# Sheet_1_2020-07-27_09-10-22.net
KiCad netlist of a schematic drawn in Altium Designer
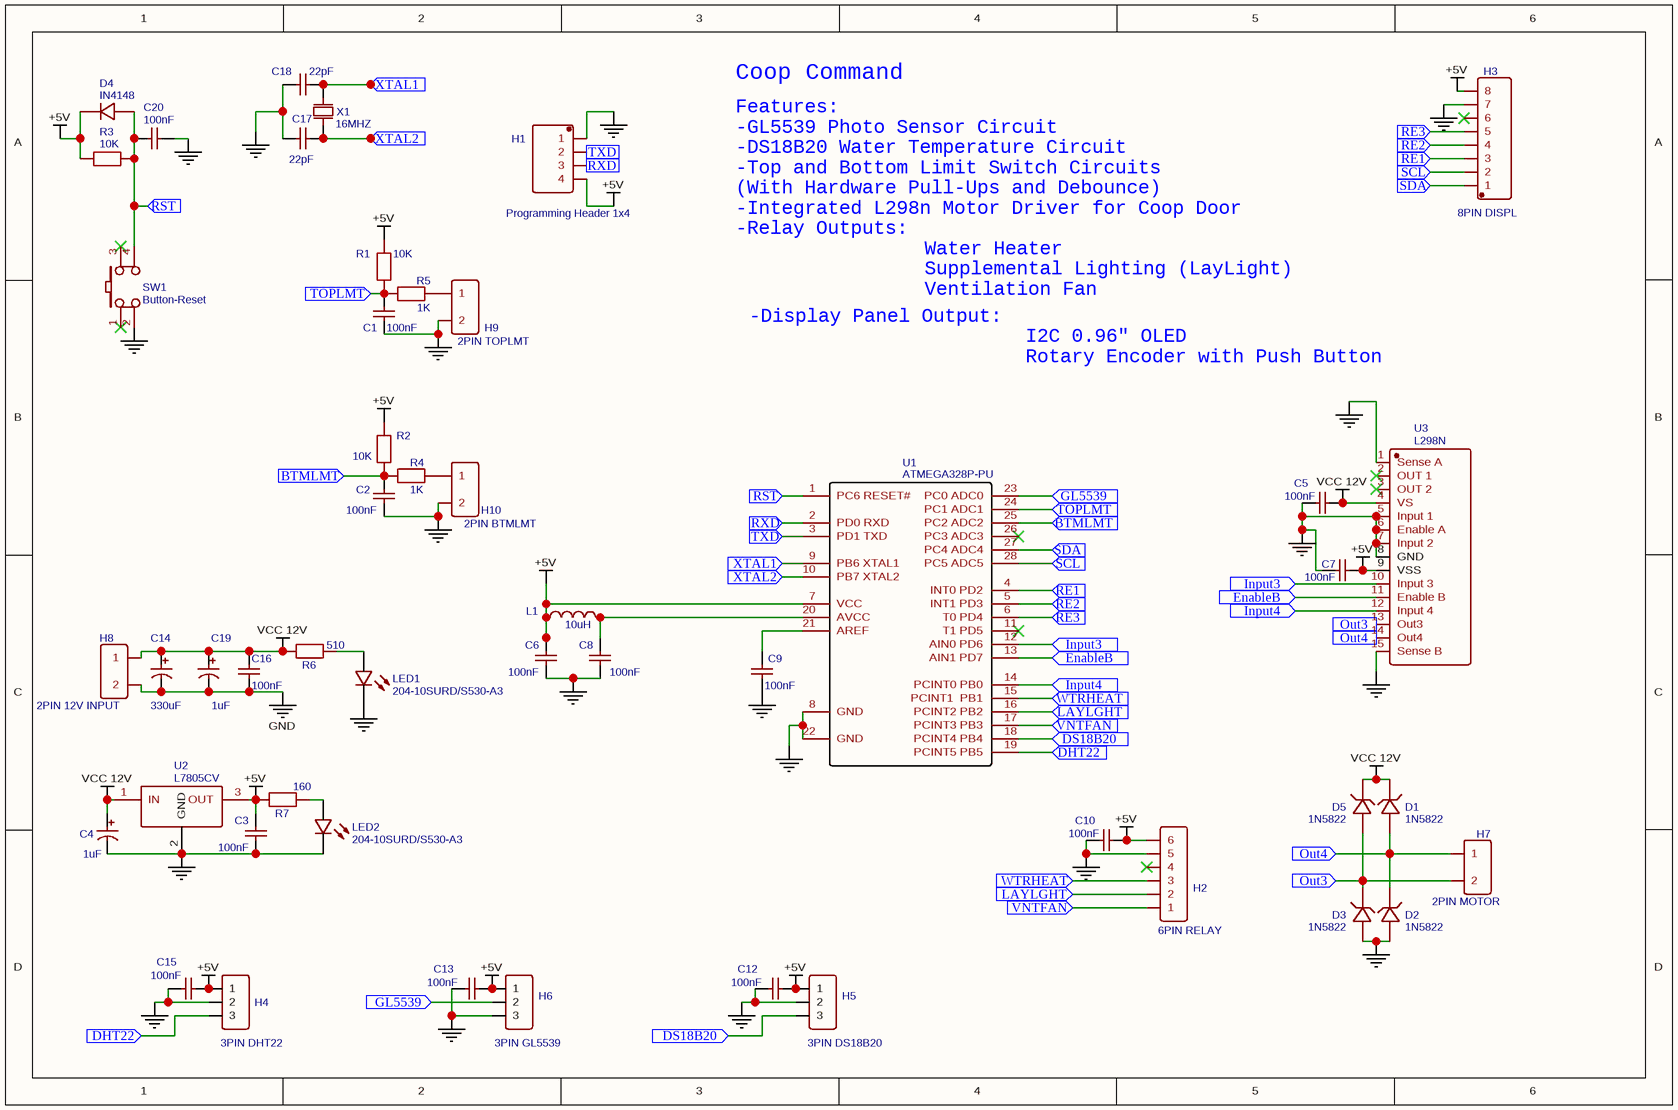
[diagram p0: Sheet_1_2020-07-27_09-10-22.schdoc]

(export (version "E")
  (design (tool "Eeschema 10.0.6"))
  (components
    (comp (ref "C1")
      (value "100nF")
      (fields
        (field (name "BOM_MANUFACTURER PART") "CS1F5.6Y5V1A104Z")
        (field (name "BOM_SUPPLIER PART") "C9306")
      )
      (libsource (lib "altium-import") (part "root_3_100nF_"))
    )
    (comp (ref "C2")
      (value "100nF")
      (fields
        (field (name "BOM_MANUFACTURER PART") "CS1F5.6Y5V1A104Z")
        (field (name "BOM_SUPPLIER PART") "C9306")
      )
      (libsource (lib "altium-import") (part "root_3_100nF_"))
    )
    (comp (ref "C3")
      (value "100nF")
      (fields
        (field (name "BOM_MANUFACTURER PART") "CS1F5.6Y5V1A104Z")
        (field (name "BOM_SUPPLIER PART") "C9306")
      )
      (libsource (lib "altium-import") (part "root_3_100nF_"))
    )
    (comp (ref "C4")
      (value "1uF")
      (fields
        (field (name "BOM_MANUFACTURER PART") "1uF 50V 4*5")
        (field (name "BOM_SUPPLIER PART") "C47848")
      )
      (libsource (lib "altium-import") (part "root_3_1uF_"))
    )
    (comp (ref "C5")
      (value "100nF")
      (fields
        (field (name "BOM_MANUFACTURER PART") "CS1F5.6Y5V1A104Z")
        (field (name "BOM_SUPPLIER PART") "C9306")
      )
      (libsource (lib "altium-import") (part "root_0_100nF_"))
    )
    (comp (ref "C6")
      (value "100nF")
      (fields
        (field (name "BOM_MANUFACTURER PART") "CS1F5.6Y5V1A104Z")
        (field (name "BOM_SUPPLIER PART") "C9306")
      )
      (libsource (lib "altium-import") (part "root_3_100nF_"))
    )
    (comp (ref "C7")
      (value "100nF")
      (fields
        (field (name "BOM_MANUFACTURER PART") "CS1F5.6Y5V1A104Z")
        (field (name "BOM_SUPPLIER PART") "C9306")
      )
      (libsource (lib "altium-import") (part "root_0_100nF_"))
    )
    (comp (ref "C8")
      (value "100nF")
      (fields
        (field (name "BOM_MANUFACTURER PART") "CS1F5.6Y5V1A104Z")
        (field (name "BOM_SUPPLIER PART") "C9306")
      )
      (libsource (lib "altium-import") (part "root_3_100nF_"))
    )
    (comp (ref "C9")
      (value "100nF")
      (fields
        (field (name "BOM_MANUFACTURER PART") "CS1F5.6Y5V1A104Z")
        (field (name "BOM_SUPPLIER PART") "C9306")
      )
      (libsource (lib "altium-import") (part "root_3_100nF_"))
    )
    (comp (ref "C10")
      (value "100nF")
      (fields
        (field (name "BOM_MANUFACTURER PART") "CS1F5.6Y5V1A104Z")
        (field (name "BOM_SUPPLIER PART") "C9306")
      )
      (libsource (lib "altium-import") (part "root_0_100nF_"))
    )
    (comp (ref "C12")
      (value "100nF")
      (fields
        (field (name "BOM_MANUFACTURER PART") "CS1F5.6Y5V1A104Z")
        (field (name "BOM_SUPPLIER PART") "C9306")
      )
      (libsource (lib "altium-import") (part "root_0_100nF_"))
    )
    (comp (ref "C13")
      (value "100nF")
      (fields
        (field (name "BOM_MANUFACTURER PART") "CS1F5.6Y5V1A104Z")
        (field (name "BOM_SUPPLIER PART") "C9306")
      )
      (libsource (lib "altium-import") (part "root_0_100nF_"))
    )
    (comp (ref "C14")
      (value "330uF")
      (fields
        (field (name "BOM_MANUFACTURER PART") "330uF 50V 10*17")
        (field (name "BOM_SUPPLIER PART") "C45107")
      )
      (libsource (lib "altium-import") (part "root_3_330uF_"))
    )
    (comp (ref "C15")
      (value "100nF")
      (fields
        (field (name "BOM_MANUFACTURER PART") "CS1F5.6Y5V1A104Z")
        (field (name "BOM_SUPPLIER PART") "C9306")
      )
      (libsource (lib "altium-import") (part "root_0_100nF_"))
    )
    (comp (ref "C16")
      (value "100nF")
      (fields
        (field (name "BOM_MANUFACTURER PART") "CS1F5.6Y5V1A104Z")
        (field (name "BOM_SUPPLIER PART") "C9306")
      )
      (libsource (lib "altium-import") (part "root_3_100nF_"))
    )
    (comp (ref "C17")
      (value "22pF")
      (fields
        (field (name "BOM_MANUFACTURER PART") "22pf/50V 10%")
        (field (name "BOM_SUPPLIER PART") "C9316")
      )
      (libsource (lib "altium-import") (part "root_0_22pF_"))
    )
    (comp (ref "C18")
      (value "22pF")
      (fields
        (field (name "BOM_MANUFACTURER PART") "22pf/50V 10%")
        (field (name "BOM_SUPPLIER PART") "C9316")
      )
      (libsource (lib "altium-import") (part "root_0_22pF_"))
    )
    (comp (ref "C19")
      (value "1uF")
      (fields
        (field (name "BOM_MANUFACTURER PART") "1uF 50V 4*5")
        (field (name "BOM_SUPPLIER PART") "C47848")
      )
      (libsource (lib "altium-import") (part "root_3_1uF_"))
    )
    (comp (ref "C20")
      (value "100nF")
      (fields
        (field (name "BOM_MANUFACTURER PART") "CS1F5.6Y5V1A104Z")
        (field (name "BOM_SUPPLIER PART") "C9306")
      )
      (libsource (lib "altium-import") (part "root_0_100nF_"))
    )
    (comp (ref "D1")
      (value "1N5822")
      (fields (field (name "BOM_SUPPLIER PART") "C402220") (field (name "CONTRIBUTOR") "LCSC"))
      (libsource (lib "") (part "root_3_1N5822__1"))
    )
    (comp (ref "D2")
      (value "1N5822")
      (fields (field (name "BOM_SUPPLIER PART") "C402220") (field (name "CONTRIBUTOR") "LCSC"))
      (libsource (lib "") (part "root_3_1N5822__1"))
    )
    (comp (ref "D3")
      (value "1N5822")
      (fields (field (name "BOM_SUPPLIER PART") "C402220") (field (name "CONTRIBUTOR") "LCSC"))
      (libsource (lib "altium-import") (part "root_3_1N5822_"))
    )
    (comp (ref "D4")
      (value "IN4148")
      (fields (field (name "BOM_SUPPLIER PART") "C14538") (field (name "CONTRIBUTOR") "LCSC"))
      (libsource (lib "altium-import") (part "root_0_IN4148_"))
    )
    (comp (ref "D5")
      (value "1N5822")
      (fields (field (name "BOM_SUPPLIER PART") "C402220") (field (name "CONTRIBUTOR") "LCSC"))
      (libsource (lib "altium-import") (part "root_3_1N5822_"))
    )
    (comp (ref "H1")
      (value "Programming Header 1x4")
      (fields
        (field (name "BOM_MANUFACTURER PART") "210S-1*4P L=11.6MMGold-plated black")
        (field (name "BOM_SUPPLIER PART") "C124378")
        (field (name "CONTRIBUTOR") "LCSC")
      )
      (libsource (lib "altium-import") (part "root_0_Programming Header 1x4_"))
    )
    (comp (ref "H2")
      (value "6PIN RELAY")
      (fields
        (field (name "BOM_MANUFACTURER PART") "Header-Male-2.54_1x6")
        (field (name "BOM_SUPPLIER PART") "C37208")
      )
      (libsource (lib "altium-import") (part "root_0_6PIN RELAY_"))
    )
    (comp (ref "H3")
      (value "8PIN DISPL")
      (fields
        (field (name "BOM_MANUFACTURER PART") "210S-1*8P L=11.6MMGold-plated black")
        (field (name "BOM_SUPPLIER PART") "C124381")
        (field (name "CONTRIBUTOR") "LCSC")
      )
      (libsource (lib "altium-import") (part "root_0_8PIN DISPL_"))
    )
    (comp (ref "H4")
      (value "3PIN DHT22")
      (fields
        (field (name "BOM_MANUFACTURER PART") "Header2.54mm 1*3P")
        (field (name "BOM_SUPPLIER PART") "C49257")
      )
      (libsource (lib "altium-import") (part "root_0_3PIN DHT22_"))
    )
    (comp (ref "H5")
      (value "3PIN DS18B20")
      (fields
        (field (name "BOM_MANUFACTURER PART") "Header2.54mm 1*3P")
        (field (name "BOM_SUPPLIER PART") "C49257")
      )
      (libsource (lib "altium-import") (part "root_0_3PIN DS18B20_"))
    )
    (comp (ref "H6")
      (value "3PIN GL5539")
      (fields
        (field (name "BOM_MANUFACTURER PART") "Header2.54mm 1*3P")
        (field (name "BOM_SUPPLIER PART") "C49257")
      )
      (libsource (lib "altium-import") (part "root_0_3PIN GL5539_"))
    )
    (comp (ref "H7")
      (value "2PIN MOTOR")
      (fields (field (name "BOM_MANUFACTURER PART") "826629-2") (field (name "BOM_SUPPLIER PART") "C86471"))
      (libsource (lib "altium-import") (part "root_0_2PIN MOTOR_"))
    )
    (comp (ref "H8")
      (value "2PIN 12V INPUT")
      (fields (field (name "BOM_MANUFACTURER PART") "826629-2") (field (name "BOM_SUPPLIER PART") "C86471"))
      (libsource (lib "altium-import") (part "root_0_2PIN 12V INPUT_"))
    )
    (comp (ref "H9")
      (value "2PIN TOPLMT")
      (fields (field (name "BOM_MANUFACTURER PART") "826629-2") (field (name "BOM_SUPPLIER PART") "C86471"))
      (libsource (lib "altium-import") (part "root_0_2PIN TOPLMT_"))
    )
    (comp (ref "H10")
      (value "2PIN BTMLMT")
      (fields (field (name "BOM_MANUFACTURER PART") "826629-2") (field (name "BOM_SUPPLIER PART") "C86471"))
      (libsource (lib "altium-import") (part "root_0_2PIN BTMLMT_"))
    )
    (comp (ref "L1")
      (value "10uH")
      (fields
        (field (name "BOM_MANUFACTURER PART") "LGA0307-100KP52E")
        (field (name "BOM_SUPPLIER PART") "C84773")
      )
      (libsource (lib "altium-import") (part "root_0_10uH_"))
    )
    (comp (ref "LED1")
      (value "204-10SURD/S530-A3")
      (fields (field (name "BOM_SUPPLIER PART") "C99772"))
      (libsource (lib "altium-import") (part "root_3_204-10SURD/S530-A3_"))
    )
    (comp (ref "LED2")
      (value "204-10SURD/S530-A3")
      (fields (field (name "BOM_SUPPLIER PART") "C99772"))
      (libsource (lib "altium-import") (part "root_3_204-10SURD/S530-A3_"))
    )
    (comp (ref "R1")
      (value "10K")
      (fields
        (field (name "BOM_SUPPLIER PART") "C410695")
        (field (name "BOM_MANUFACTURER PART") "RN 1/4W 10K F T/B A1")
        (field (name "CONTRIBUTOR") "LCSC")
      )
      (libsource (lib "altium-import") (part "root_1_10K_"))
    )
    (comp (ref "R2")
      (value "10K")
      (fields
        (field (name "BOM_SUPPLIER PART") "C410695")
        (field (name "BOM_MANUFACTURER PART") "RN 1/4W 10K F T/B A1")
        (field (name "CONTRIBUTOR") "LCSC")
      )
      (libsource (lib "altium-import") (part "root_1_10K_"))
    )
    (comp (ref "R3")
      (value "10K")
      (fields
        (field (name "BOM_SUPPLIER PART") "C410695")
        (field (name "BOM_MANUFACTURER PART") "RN 1/4W 10K F T/B A1")
        (field (name "CONTRIBUTOR") "LCSC")
      )
      (libsource (lib "altium-import") (part "root_2_10K_"))
    )
    (comp (ref "R4")
      (value "1K")
      (fields
        (field (name "BOM_SUPPLIER PART") "C410696")
        (field (name "BOM_MANUFACTURER PART") "RN 1/4W 1K F T/B A1")
        (field (name "CONTRIBUTOR") "LCSC")
      )
      (libsource (lib "altium-import") (part "root_0_1K_"))
    )
    (comp (ref "R5")
      (value "1K")
      (fields
        (field (name "BOM_SUPPLIER PART") "C410696")
        (field (name "BOM_MANUFACTURER PART") "RN 1/4W 1K F T/B A1")
        (field (name "CONTRIBUTOR") "LCSC")
      )
      (libsource (lib "altium-import") (part "root_0_1K_"))
    )
    (comp (ref "R6")
      (value "510")
      (fields
        (field (name "BOM_SUPPLIER PART") "C433511")
        (field (name "BOM_MANUFACTURER PART") "RN 1/2WS 510R F T/B A1")
        (field (name "CONTRIBUTOR") "LCSC")
      )
      (libsource (lib "altium-import") (part "root_0_510_"))
    )
    (comp (ref "R7")
      (value "160")
      (fields
        (field (name "BOM_SUPPLIER PART") "C410672")
        (field (name "BOM_MANUFACTURER PART") "RN 1/4W 160R F T/B A1")
        (field (name "CONTRIBUTOR") "LCSC")
      )
      (libsource (lib "altium-import") (part "root_0_160_"))
    )
    (comp (ref "SW1")
      (value "Button-Reset")
      (fields
        (field (name "BOM_SUPPLIER PART") "C71836")
        (field (name "BOM_MANUFACTURER PART") "Switch,6*6*6Plastic head,260G, 0.25mm,Straight line")
      )
      (libsource (lib "altium-import") (part "root_1_Button-Reset_"))
    )
    (comp (ref "U1")
      (value "ATMEGA328P-PU")
      (fields (field (name "BOM_SUPPLIER PART") "C33901") (field (name "CONTRIBUTOR") "LCSC"))
      (libsource (lib "altium-import") (part "root_0_ATMEGA328P-PU_"))
    )
    (comp (ref "U2")
      (value "L7805CV")
      (fields (field (name "BOM_SUPPLIER PART") "C111887"))
      (libsource (lib "altium-import") (part "root_0_L7805CV_"))
    )
    (comp (ref "U3")
      (value "L298N")
      (fields (field (name "BOM_SUPPLIER PART") "C434589") (field (name "CONTRIBUTOR") "LCSC"))
      (libsource (lib "altium-import") (part "root_0_L298N_"))
    )
    (comp (ref "X1")
      (value "16MHZ")
      (fields
        (field (name "BOM_SUPPLIER PART") "C389708")
        (field (name "BOM_MANUFACTURER PART") "5S0-1600A1620-00")
        (field (name "CONTRIBUTOR") "LCSC")
      )
      (libsource (lib "altium-import") (part "root_3_16MHZ_"))
    )
  )
  (nets
    (net (code "1") (name "+5V") (class "Default")
      (node (ref "C10") (pin "2") (pinfunction "2_2") (pintype "passive"))
      (node (ref "C12") (pin "2") (pinfunction "2_2") (pintype "passive"))
      (node (ref "C13") (pin "2") (pinfunction "2_2") (pintype "passive"))
      (node (ref "C15") (pin "2") (pinfunction "2_2") (pintype "passive"))
      (node (ref "C3") (pin "1") (pinfunction "1_1") (pintype "passive"))
      (node (ref "C6") (pin "1") (pinfunction "1_1") (pintype "passive"))
      (node (ref "C7") (pin "2") (pinfunction "2_2") (pintype "passive"))
      (node (ref "D4") (pin "1") (pinfunction "1_1") (pintype "passive"))
      (node (ref "H1") (pin "4") (pinfunction "4_4") (pintype "passive"))
      (node (ref "H2") (pin "6") (pinfunction "6_6") (pintype "passive"))
      (node (ref "H3") (pin "8") (pinfunction "8_8") (pintype "passive"))
      (node (ref "H4") (pin "1") (pinfunction "1_1") (pintype "passive"))
      (node (ref "H5") (pin "1") (pinfunction "1_1") (pintype "passive"))
      (node (ref "H6") (pin "1") (pinfunction "1_1") (pintype "passive"))
      (node (ref "L1") (pin "1") (pinfunction "1_1") (pintype "passive"))
      (node (ref "R1") (pin "2") (pinfunction "2_2") (pintype "passive"))
      (node (ref "R2") (pin "2") (pinfunction "2_2") (pintype "passive"))
      (node (ref "R3") (pin "2") (pinfunction "2_2") (pintype "passive"))
      (node (ref "R7") (pin "1") (pinfunction "1_1") (pintype "passive"))
      (node (ref "U1") (pin "7") (pinfunction "VCC_7") (pintype "passive"))
      (node (ref "U2") (pin "3") (pinfunction "OUT_3") (pintype "passive"))
      (node (ref "U3") (pin "9") (pinfunction "VSS_9") (pintype "passive"))
    )
    (net (code "2") (name "/BTMLMT") (class "Default")
      (node (ref "C2") (pin "1") (pinfunction "1_1") (pintype "passive"))
      (node (ref "R2") (pin "1") (pinfunction "1_1") (pintype "passive"))
      (node (ref "R4") (pin "1") (pinfunction "1_1") (pintype "passive"))
      (node (ref "U1") (pin "25") (pinfunction "PC2_ADC2_25") (pintype "passive"))
    )
    (net (code "3") (name "/DHT22") (class "Default")
      (node (ref "H4") (pin "3") (pinfunction "3_3") (pintype "passive"))
      (node (ref "U1") (pin "19") (pinfunction "PCINT5_PB5_19") (pintype "passive"))
    )
    (net (code "4") (name "/DS18B20") (class "Default")
      (node (ref "H5") (pin "3") (pinfunction "3_3") (pintype "passive"))
      (node (ref "U1") (pin "18") (pinfunction "PCINT4_PB4_18") (pintype "passive"))
    )
    (net (code "5") (name "/EnableB") (class "Default")
      (node (ref "U1") (pin "13") (pinfunction "AIN1_PD7_13") (pintype "passive"))
      (node (ref "U3") (pin "11") (pinfunction "Enable_B_11") (pintype "passive"))
    )
    (net (code "6") (name "/GL5539") (class "Default")
      (node (ref "H6") (pin "2") (pinfunction "2_2") (pintype "passive"))
      (node (ref "U1") (pin "23") (pinfunction "PC0_ADC0_23") (pintype "passive"))
    )
    (net (code "7") (name "/Input3") (class "Default")
      (node (ref "U1") (pin "12") (pinfunction "AIN0_PD6_12") (pintype "passive"))
      (node (ref "U3") (pin "10") (pinfunction "Input_3_10") (pintype "passive"))
    )
    (net (code "8") (name "/Input4") (class "Default")
      (node (ref "U1") (pin "14") (pinfunction "PCINT0_PB0_14") (pintype "passive"))
      (node (ref "U3") (pin "12") (pinfunction "Input_4_12") (pintype "passive"))
    )
    (net (code "9") (name "/LAYLGHT") (class "Default")
      (node (ref "H2") (pin "2") (pinfunction "2_2") (pintype "passive"))
      (node (ref "U1") (pin "16") (pinfunction "PCINT2_PB2_16") (pintype "passive"))
    )
    (net (code "10") (name "/Out3") (class "Default")
      (node (ref "D3") (pin "1") (pinfunction "C_1") (pintype "passive"))
      (node (ref "D5") (pin "2") (pinfunction "A_2") (pintype "passive"))
      (node (ref "H7") (pin "2") (pinfunction "2_2") (pintype "passive"))
      (node (ref "U3") (pin "13") (pinfunction "Out3_13") (pintype "passive"))
    )
    (net (code "11") (name "/Out4") (class "Default")
      (node (ref "D1") (pin "2") (pinfunction "A_2") (pintype "passive"))
      (node (ref "D2") (pin "1") (pinfunction "C_1") (pintype "passive"))
      (node (ref "H7") (pin "1") (pinfunction "1_1") (pintype "passive"))
      (node (ref "U3") (pin "14") (pinfunction "Out4_14") (pintype "passive"))
    )
    (net (code "12") (name "/RE1") (class "Default")
      (node (ref "H3") (pin "3") (pinfunction "3_3") (pintype "passive"))
      (node (ref "U1") (pin "4") (pinfunction "INT0_PD2_4") (pintype "passive"))
    )
    (net (code "13") (name "/RE2") (class "Default")
      (node (ref "H3") (pin "4") (pinfunction "4_4") (pintype "passive"))
      (node (ref "U1") (pin "5") (pinfunction "INT1_PD3_5") (pintype "passive"))
    )
    (net (code "14") (name "/RE3") (class "Default")
      (node (ref "H3") (pin "5") (pinfunction "5_5") (pintype "passive"))
      (node (ref "U1") (pin "6") (pinfunction "T0_PD4_6") (pintype "passive"))
    )
    (net (code "15") (name "/RST") (class "Default")
      (node (ref "C20") (pin "1") (pinfunction "1_1") (pintype "passive"))
      (node (ref "D4") (pin "2") (pinfunction "2_2") (pintype "passive"))
      (node (ref "R3") (pin "1") (pinfunction "1_1") (pintype "passive"))
      (node (ref "SW1") (pin "4") (pinfunction "4_4") (pintype "passive"))
      (node (ref "U1") (pin "1") (pinfunction "PC6_RESET#_1") (pintype "passive"))
    )
    (net (code "16") (name "/RXD") (class "Default")
      (node (ref "H1") (pin "3") (pinfunction "3_3") (pintype "passive"))
      (node (ref "U1") (pin "2") (pinfunction "PD0_RXD_2") (pintype "passive"))
    )
    (net (code "17") (name "/SCL") (class "Default")
      (node (ref "H3") (pin "2") (pinfunction "2_2") (pintype "passive"))
      (node (ref "U1") (pin "28") (pinfunction "PC5_ADC5_28") (pintype "passive"))
    )
    (net (code "18") (name "/SDA") (class "Default")
      (node (ref "H3") (pin "1") (pinfunction "1_1") (pintype "passive"))
      (node (ref "U1") (pin "27") (pinfunction "PC4_ADC4_27") (pintype "passive"))
    )
    (net (code "19") (name "/TOPLMT") (class "Default")
      (node (ref "C1") (pin "1") (pinfunction "1_1") (pintype "passive"))
      (node (ref "R1") (pin "1") (pinfunction "1_1") (pintype "passive"))
      (node (ref "R5") (pin "1") (pinfunction "1_1") (pintype "passive"))
      (node (ref "U1") (pin "24") (pinfunction "PC1_ADC1_24") (pintype "passive"))
    )
    (net (code "20") (name "/TXD") (class "Default")
      (node (ref "H1") (pin "2") (pinfunction "2_2") (pintype "passive"))
      (node (ref "U1") (pin "3") (pinfunction "PD1_TXD_3") (pintype "passive"))
    )
    (net (code "21") (name "/VNTFAN") (class "Default")
      (node (ref "H2") (pin "1") (pinfunction "1_1") (pintype "passive"))
      (node (ref "U1") (pin "17") (pinfunction "PCINT3_PB3_17") (pintype "passive"))
    )
    (net (code "22") (name "/WTRHEAT") (class "Default")
      (node (ref "H2") (pin "3") (pinfunction "3_3") (pintype "passive"))
      (node (ref "U1") (pin "15") (pinfunction "PCINT1__PB1_15") (pintype "passive"))
    )
    (net (code "23") (name "/XTAL1") (class "Default")
      (node (ref "C18") (pin "2") (pinfunction "2_2") (pintype "passive"))
      (node (ref "U1") (pin "9") (pinfunction "PB6_XTAL1_9") (pintype "passive"))
      (node (ref "X1") (pin "1") (pinfunction "OSC1_1") (pintype "passive"))
    )
    (net (code "24") (name "/XTAL2") (class "Default")
      (node (ref "C17") (pin "2") (pinfunction "2_2") (pintype "passive"))
      (node (ref "U1") (pin "10") (pinfunction "PB7_XTAL2_10") (pintype "passive"))
      (node (ref "X1") (pin "2") (pinfunction "OSC2_2") (pintype "passive"))
    )
    (net (code "25") (name "GND") (class "Default")
      (node (ref "C1") (pin "2") (pinfunction "2_2") (pintype "passive"))
      (node (ref "C10") (pin "1") (pinfunction "1_1") (pintype "passive"))
      (node (ref "C12") (pin "1") (pinfunction "1_1") (pintype "passive"))
      (node (ref "C13") (pin "1") (pinfunction "1_1") (pintype "passive"))
      (node (ref "C14") (pin "2") (pinfunction "2_2") (pintype "passive"))
      (node (ref "C15") (pin "1") (pinfunction "1_1") (pintype "passive"))
      (node (ref "C16") (pin "2") (pinfunction "2_2") (pintype "passive"))
      (node (ref "C17") (pin "1") (pinfunction "1_1") (pintype "passive"))
      (node (ref "C18") (pin "1") (pinfunction "1_1") (pintype "passive"))
      (node (ref "C19") (pin "2") (pinfunction "2_2") (pintype "passive"))
      (node (ref "C2") (pin "2") (pinfunction "2_2") (pintype "passive"))
      (node (ref "C20") (pin "2") (pinfunction "2_2") (pintype "passive"))
      (node (ref "C3") (pin "2") (pinfunction "2_2") (pintype "passive"))
      (node (ref "C4") (pin "2") (pinfunction "2_2") (pintype "passive"))
      (node (ref "C5") (pin "1") (pinfunction "1_1") (pintype "passive"))
      (node (ref "C6") (pin "2") (pinfunction "2_2") (pintype "passive"))
      (node (ref "C7") (pin "1") (pinfunction "1_1") (pintype "passive"))
      (node (ref "C8") (pin "2") (pinfunction "2_2") (pintype "passive"))
      (node (ref "C9") (pin "2") (pinfunction "2_2") (pintype "passive"))
      (node (ref "D2") (pin "2") (pinfunction "A_2") (pintype "passive"))
      (node (ref "D3") (pin "2") (pinfunction "A_2") (pintype "passive"))
      (node (ref "H1") (pin "1") (pinfunction "1_1") (pintype "passive"))
      (node (ref "H10") (pin "2") (pinfunction "2_2") (pintype "passive"))
      (node (ref "H2") (pin "5") (pinfunction "5_5") (pintype "passive"))
      (node (ref "H3") (pin "7") (pinfunction "7_7") (pintype "passive"))
      (node (ref "H4") (pin "2") (pinfunction "2_2") (pintype "passive"))
      (node (ref "H5") (pin "2") (pinfunction "2_2") (pintype "passive"))
      (node (ref "H6") (pin "3") (pinfunction "3_3") (pintype "passive"))
      (node (ref "H8") (pin "2") (pinfunction "2_2") (pintype "passive"))
      (node (ref "H9") (pin "2") (pinfunction "2_2") (pintype "passive"))
      (node (ref "LED1") (pin "2") (pinfunction "K_2") (pintype "passive"))
      (node (ref "LED2") (pin "2") (pinfunction "K_2") (pintype "passive"))
      (node (ref "SW1") (pin "2") (pinfunction "2_2") (pintype "passive"))
      (node (ref "U1") (pin "22") (pinfunction "GND_22") (pintype "passive"))
      (node (ref "U1") (pin "8") (pinfunction "GND_8") (pintype "passive"))
      (node (ref "U2") (pin "2") (pinfunction "GND_2") (pintype "passive"))
      (node (ref "U3") (pin "1") (pinfunction "Sense_A_1") (pintype "passive"))
      (node (ref "U3") (pin "15") (pinfunction "Sense_B_15") (pintype "passive"))
      (node (ref "U3") (pin "5") (pinfunction "Input_1_5") (pintype "passive"))
      (node (ref "U3") (pin "6") (pinfunction "Enable_A_6") (pintype "passive"))
      (node (ref "U3") (pin "7") (pinfunction "Input_2_7") (pintype "passive"))
      (node (ref "U3") (pin "8") (pinfunction "GND_8") (pintype "passive"))
    )
    (net (code "26") (name "Net-(H9-Pad1)") (class "Default")
      (node (ref "H9") (pin "1") (pinfunction "1_1") (pintype "passive"))
      (node (ref "R5") (pin "2") (pinfunction "2_2") (pintype "passive"))
    )
    (net (code "27") (name "Net-(H10-Pad1)") (class "Default")
      (node (ref "H10") (pin "1") (pinfunction "1_1") (pintype "passive"))
      (node (ref "R4") (pin "2") (pinfunction "2_2") (pintype "passive"))
    )
    (net (code "28") (name "Net-(LED1-A)") (class "Default")
      (node (ref "LED1") (pin "1") (pinfunction "A_1") (pintype "passive"))
      (node (ref "R6") (pin "2") (pinfunction "2_2") (pintype "passive"))
    )
    (net (code "29") (name "Net-(LED2-A)") (class "Default")
      (node (ref "LED2") (pin "1") (pinfunction "A_1") (pintype "passive"))
      (node (ref "R7") (pin "2") (pinfunction "2_2") (pintype "passive"))
    )
    (net (code "30") (name "Net-(U1-AREF)") (class "Default")
      (node (ref "C9") (pin "1") (pinfunction "1_1") (pintype "passive"))
      (node (ref "U1") (pin "21") (pinfunction "AREF_21") (pintype "passive"))
    )
    (net (code "31") (name "Net-(U1-AVCC)") (class "Default")
      (node (ref "C8") (pin "1") (pinfunction "1_1") (pintype "passive"))
      (node (ref "L1") (pin "2") (pinfunction "2_2") (pintype "passive"))
      (node (ref "U1") (pin "20") (pinfunction "AVCC_20") (pintype "passive"))
    )
    (net (code "32") (name "VCC 12V") (class "Default")
      (node (ref "C14") (pin "1") (pinfunction "1_1") (pintype "passive"))
      (node (ref "C16") (pin "1") (pinfunction "1_1") (pintype "passive"))
      (node (ref "C19") (pin "1") (pinfunction "1_1") (pintype "passive"))
      (node (ref "C4") (pin "1") (pinfunction "1_1") (pintype "passive"))
      (node (ref "C5") (pin "2") (pinfunction "2_2") (pintype "passive"))
      (node (ref "D1") (pin "1") (pinfunction "C_1") (pintype "passive"))
      (node (ref "D5") (pin "1") (pinfunction "C_1") (pintype "passive"))
      (node (ref "H8") (pin "1") (pinfunction "1_1") (pintype "passive"))
      (node (ref "R6") (pin "1") (pinfunction "1_1") (pintype "passive"))
      (node (ref "U2") (pin "1") (pinfunction "IN_1") (pintype "passive"))
      (node (ref "U3") (pin "4") (pinfunction "VS_4") (pintype "passive"))
    )
    (net (code "33") (name "unconnected-(H2-Pad4)") (class "Default")
      (node (ref "H2") (pin "4") (pinfunction "4_4") (pintype "passive+no_connect"))
    )
    (net (code "34") (name "unconnected-(H3-Pad6)") (class "Default")
      (node (ref "H3") (pin "6") (pinfunction "6_6") (pintype "passive+no_connect"))
    )
    (net (code "35") (name "unconnected-(SW1-Pad1)") (class "Default")
      (node (ref "SW1") (pin "1") (pinfunction "1_1") (pintype "passive+no_connect"))
    )
    (net (code "36") (name "unconnected-(SW1-Pad3)") (class "Default")
      (node (ref "SW1") (pin "3") (pinfunction "3_3") (pintype "passive+no_connect"))
    )
    (net (code "37") (name "unconnected-(U1-PC3_ADC3-Pad26)") (class "Default")
      (node (ref "U1") (pin "26") (pinfunction "PC3_ADC3_26") (pintype "passive+no_connect"))
    )
    (net (code "38") (name "unconnected-(U1-T1_PD5-Pad11)") (class "Default")
      (node (ref "U1") (pin "11") (pinfunction "T1_PD5_11") (pintype "passive+no_connect"))
    )
    (net (code "39") (name "unconnected-(U3-OUT_1-Pad2)") (class "Default")
      (node (ref "U3") (pin "2") (pinfunction "OUT_1_2") (pintype "passive+no_connect"))
    )
    (net (code "40") (name "unconnected-(U3-OUT_2-Pad3)") (class "Default")
      (node (ref "U3") (pin "3") (pinfunction "OUT_2_3") (pintype "passive+no_connect"))
    )
  )
)
